# fm_transmitter.net
KiCad netlist of a schematic drawn in EAGLE
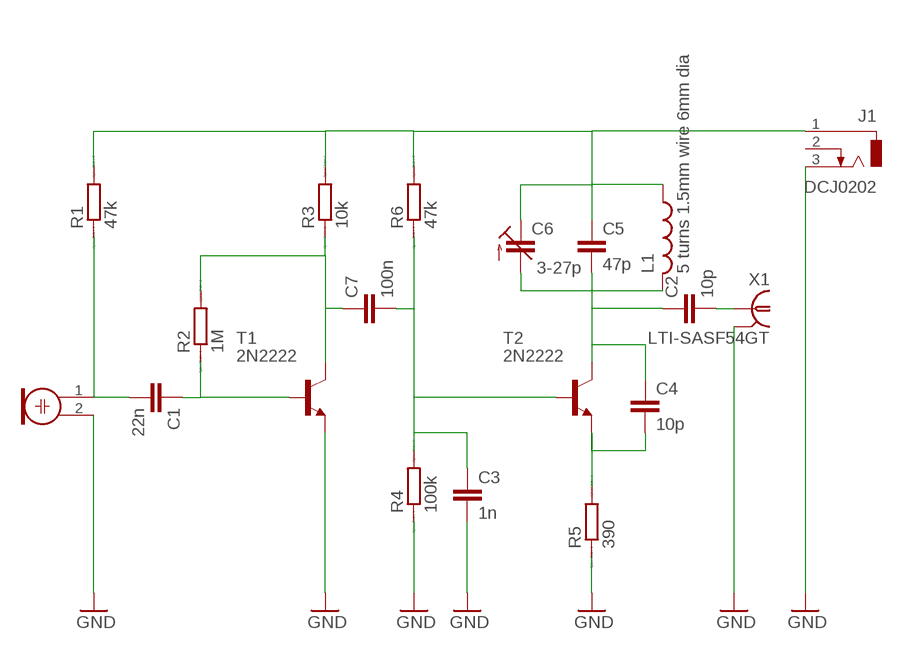
[diagram p0: schematic, sheet 1]

(export (version "E")
  (design (tool "Eeschema 10.0.6"))
  (components
    (comp (ref "C1")
      (value "22n")
      (footprint "eagle-import:C2.5-4")
      (libsource (lib "eagle-import") (part "C2.5/4"))
    )
    (comp (ref "C2")
      (value "10p")
      (footprint "eagle-import:C2.5-4")
      (libsource (lib "eagle-import") (part "C2.5/4"))
    )
    (comp (ref "C3")
      (value "1n")
      (footprint "eagle-import:C2.5-4")
      (libsource (lib "eagle-import") (part "C2.5/4"))
    )
    (comp (ref "C4")
      (value "10p")
      (footprint "eagle-import:C2.5-4")
      (libsource (lib "eagle-import") (part "C2.5/4"))
    )
    (comp (ref "C5")
      (value "47p")
      (footprint "eagle-import:C2.5-4")
      (libsource (lib "eagle-import") (part "C2.5/4"))
    )
    (comp (ref "C6")
      (value "3-27p")
      (footprint "eagle-import:3008")
      (libsource (lib "eagle-import") (part "C-TRIMM3008"))
    )
    (comp (ref "C7")
      (value "100n")
      (footprint "eagle-import:C2.5-4")
      (libsource (lib "eagle-import") (part "C2.5/4"))
    )
    (comp (ref "J1")
      (value "DCJ0202")
      (footprint "eagle-import:DCJ0202")
      (libsource (lib "eagle-import") (part "DCJ0202"))
    )
    (comp (ref "L1")
      (value "5 turns 1.5mm wire 6mm dia")
      (footprint "eagle-import:0207_7")
      (libsource (lib "eagle-import") (part "L-US0207/7"))
    )
    (comp (ref "M1")
      (value "ELECTRET_MICROPHON-F6050AP")
      (footprint "eagle-import:F6050AP")
      (libsource (lib "eagle-import") (part "ELECTRET_MICROPHON-F6050AP"))
    )
    (comp (ref "R1")
      (value "47k")
      (footprint "eagle-import:0207_10")
      (libsource (lib "eagle-import") (part "R0207/10"))
    )
    (comp (ref "R2")
      (value "1M")
      (footprint "eagle-import:0207_10")
      (libsource (lib "eagle-import") (part "R0207/10"))
    )
    (comp (ref "R3")
      (value "10k")
      (footprint "eagle-import:0207_10")
      (libsource (lib "eagle-import") (part "R0207/10"))
    )
    (comp (ref "R4")
      (value "100k")
      (footprint "eagle-import:0207_10")
      (libsource (lib "eagle-import") (part "R0207/10"))
    )
    (comp (ref "R5")
      (value "390")
      (footprint "eagle-import:0207_10")
      (libsource (lib "eagle-import") (part "R0207/10"))
    )
    (comp (ref "R6")
      (value "47k")
      (footprint "eagle-import:0207_10")
      (libsource (lib "eagle-import") (part "R0207/10"))
    )
    (comp (ref "T1")
      (value "2N2222")
      (footprint "eagle-import:TO18")
      (libsource (lib "eagle-import") (part "2N2222"))
    )
    (comp (ref "T2")
      (value "2N2222")
      (footprint "eagle-import:TO18")
      (libsource (lib "eagle-import") (part "2N2222"))
    )
    (comp (ref "X1")
      (value "LTI-SASF54GT")
      (footprint "eagle-import:LTI-SASF54GT")
      (libsource (lib "eagle-import") (part "LTI-SASF54GT"))
    )
  )
  (nets
    (net (code "1") (name "GND") (class "Default")
      (node (ref "C3") (pin "2") (pinfunction "2_2") (pintype "passive"))
      (node (ref "J1") (pin "3") (pinfunction "3_3") (pintype "passive"))
      (node (ref "M1") (pin "2") (pinfunction "2_2") (pintype "passive"))
      (node (ref "R4") (pin "1") (pinfunction "1_1") (pintype "passive"))
      (node (ref "R5") (pin "1") (pinfunction "1_1") (pintype "passive"))
      (node (ref "T1") (pin "1") (pinfunction "E_1") (pintype "passive"))
      (node (ref "X1") (pin "2") (pinfunction "2_2") (pintype "passive"))
      (node (ref "X1") (pin "3") (pinfunction "2_3") (pintype "passive"))
      (node (ref "X1") (pin "4") (pinfunction "2_4") (pintype "passive"))
      (node (ref "X1") (pin "5") (pinfunction "2_5") (pintype "passive"))
    )
    (net (code "2") (name "Net-(C1-Pad2)") (class "Default")
      (node (ref "C1") (pin "2") (pinfunction "2_2") (pintype "passive"))
      (node (ref "M1") (pin "1") (pinfunction "1_1") (pintype "passive"))
      (node (ref "R1") (pin "1") (pinfunction "1_1") (pintype "passive"))
    )
    (net (code "3") (name "Net-(C2-Pad2)") (class "Default")
      (node (ref "C2") (pin "2") (pinfunction "2_2") (pintype "passive"))
      (node (ref "X1") (pin "1") (pinfunction "1_1") (pintype "passive"))
    )
    (net (code "4") (name "Net-(C6-A)") (class "Default")
      (node (ref "C2") (pin "1") (pinfunction "1_1") (pintype "passive"))
      (node (ref "C4") (pin "1") (pinfunction "1_1") (pintype "passive"))
      (node (ref "C5") (pin "2") (pinfunction "2_2") (pintype "passive"))
      (node (ref "C6") (pin "-") (pinfunction "A_-") (pintype "passive"))
      (node (ref "L1") (pin "2") (pinfunction "2_2") (pintype "passive"))
      (node (ref "T2") (pin "3") (pinfunction "C_3") (pintype "passive"))
    )
    (net (code "5") (name "Net-(C6-E)") (class "Default")
      (node (ref "C5") (pin "1") (pinfunction "1_1") (pintype "passive"))
      (node (ref "C6") (pin "+") (pinfunction "E_+") (pintype "passive"))
      (node (ref "J1") (pin "1") (pinfunction "1_1") (pintype "passive"))
      (node (ref "L1") (pin "1") (pinfunction "1_1") (pintype "passive"))
      (node (ref "R1") (pin "2") (pinfunction "2_2") (pintype "passive"))
      (node (ref "R3") (pin "2") (pinfunction "2_2") (pintype "passive"))
      (node (ref "R6") (pin "2") (pinfunction "2_2") (pintype "passive"))
    )
    (net (code "6") (name "Net-(T1-B)") (class "Default")
      (node (ref "C1") (pin "1") (pinfunction "1_1") (pintype "passive"))
      (node (ref "R2") (pin "1") (pinfunction "1_1") (pintype "passive"))
      (node (ref "T1") (pin "2") (pinfunction "B_2") (pintype "passive"))
    )
    (net (code "7") (name "Net-(T1-C)") (class "Default")
      (node (ref "C7") (pin "1") (pinfunction "1_1") (pintype "passive"))
      (node (ref "R2") (pin "2") (pinfunction "2_2") (pintype "passive"))
      (node (ref "R3") (pin "1") (pinfunction "1_1") (pintype "passive"))
      (node (ref "T1") (pin "3") (pinfunction "C_3") (pintype "passive"))
    )
    (net (code "8") (name "Net-(T2-B)") (class "Default")
      (node (ref "C3") (pin "1") (pinfunction "1_1") (pintype "passive"))
      (node (ref "C7") (pin "2") (pinfunction "2_2") (pintype "passive"))
      (node (ref "R4") (pin "2") (pinfunction "2_2") (pintype "passive"))
      (node (ref "R6") (pin "1") (pinfunction "1_1") (pintype "passive"))
      (node (ref "T2") (pin "2") (pinfunction "B_2") (pintype "passive"))
    )
    (net (code "9") (name "Net-(T2-E)") (class "Default")
      (node (ref "C4") (pin "2") (pinfunction "2_2") (pintype "passive"))
      (node (ref "R5") (pin "2") (pinfunction "2_2") (pintype "passive"))
      (node (ref "T2") (pin "1") (pinfunction "E_1") (pintype "passive"))
    )
    (net (code "10") (name "unconnected-(J1-Pad2)") (class "Default")
      (node (ref "J1") (pin "2") (pinfunction "2_2") (pintype "passive"))
    )
  )
)
